# audioconnect.net
KiCad netlist of a schematic drawn in EAGLE
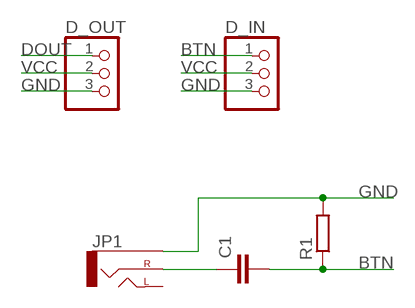
[diagram p0: schematic, sheet 1]

(export (version "E")
  (design (tool "Eeschema 10.0.6"))
  (components
    (comp (ref "C1")
      (value "C-EUC1206")
      (footprint "eagle-import:C1206")
      (libsource (lib "eagle-import") (part "C-EUC1206"))
    )
    (comp (ref "D_IN")
      (value "PINHD-1X03_2.54-S")
      (footprint "eagle-import:1X03-S")
      (libsource (lib "eagle-import") (part "PINHD-1X03_2.54-S"))
    )
    (comp (ref "D_OUT")
      (value "PINHD-1X03_2.54-S")
      (footprint "eagle-import:1X03-S")
      (libsource (lib "eagle-import") (part "PINHD-1X03_2.54-S"))
    )
    (comp (ref "JP1")
      (value "AUDIO-JACKPTH")
      (footprint "eagle-import:AUDIO-JACK")
      (libsource (lib "eagle-import") (part "AUDIO-JACKPTH"))
    )
    (comp (ref "R1")
      (value "R-EU_R1206")
      (footprint "eagle-import:R1206")
      (libsource (lib "eagle-import") (part "R-EU_R1206"))
    )
  )
  (nets
    (net (code "1") (name "/BTN") (class "Default")
      (node (ref "C1") (pin "2") (pinfunction "2_2") (pintype "passive"))
      (node (ref "D_IN") (pin "1") (pinfunction "1_1") (pintype "passive"))
      (node (ref "R1") (pin "1") (pinfunction "1_1") (pintype "passive"))
    )
    (net (code "2") (name "/DOUT") (class "Default")
      (node (ref "D_OUT") (pin "1") (pinfunction "1_1") (pintype "passive"))
    )
    (net (code "3") (name "/GND") (class "Default")
      (node (ref "D_IN") (pin "3") (pinfunction "3_3") (pintype "passive"))
      (node (ref "D_OUT") (pin "3") (pinfunction "3_3") (pintype "passive"))
      (node (ref "JP1") (pin "SLEEVE") (pinfunction "SLEEVE_SLEEVE") (pintype "bidirectional"))
      (node (ref "R1") (pin "2") (pinfunction "2_2") (pintype "passive"))
    )
    (net (code "4") (name "/VCC") (class "Default")
      (node (ref "D_IN") (pin "2") (pinfunction "2_2") (pintype "passive"))
      (node (ref "D_OUT") (pin "2") (pinfunction "2_2") (pintype "passive"))
    )
    (net (code "5") (name "Net-(JP1-RIGHT)") (class "Default")
      (node (ref "C1") (pin "1") (pinfunction "1_1") (pintype "passive"))
      (node (ref "JP1") (pin "RING") (pinfunction "RIGHT_RING") (pintype "bidirectional"))
    )
    (net (code "6") (name "unconnected-(JP1-LEFT-PadTIP)") (class "Default")
      (node (ref "JP1") (pin "TIP") (pinfunction "LEFT_TIP") (pintype "bidirectional"))
    )
  )
)
